# MachTestNguonSanXuat31072019.net
KiCad netlist of a schematic drawn in EAGLE
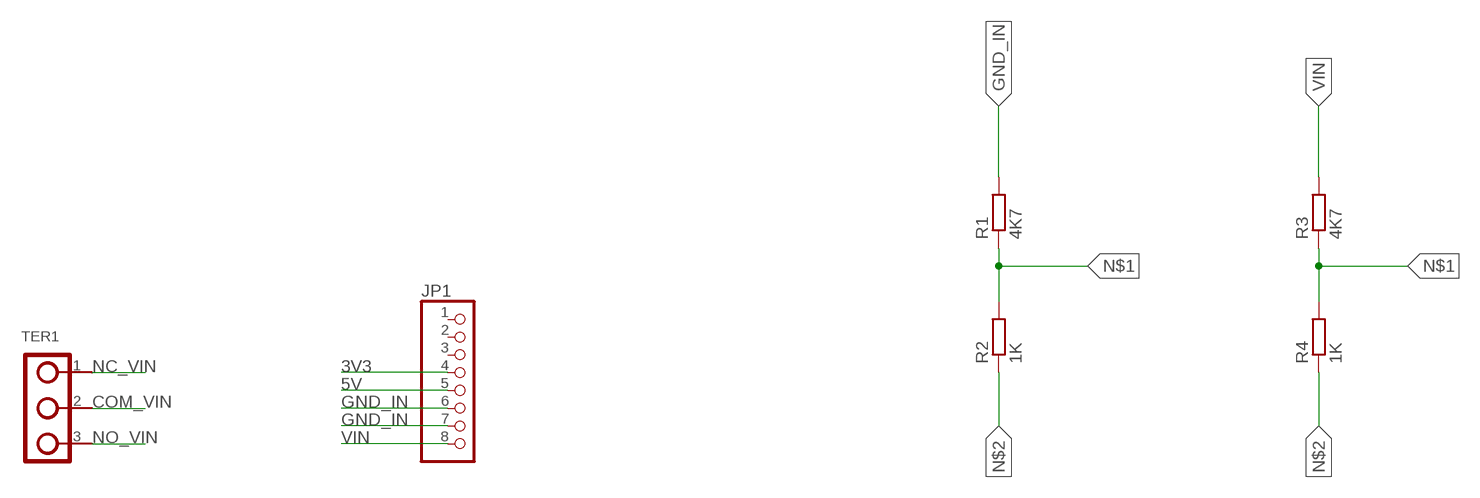
[diagram p0: schematic, sheet 1]

(export (version "E")
  (design (tool "Eeschema 10.0.6"))
  (components
    (comp (ref "JP1")
      (value "PINHD-1X8CLEANBIG")
      (footprint "eagle-import:1X08-CLEANBIG")
      (libsource (lib "eagle-import") (part "PINHD-1X8CLEANBIG"))
    )
    (comp (ref "R1")
      (value "4K7")
      (footprint "eagle-import:RCL_R0603")
      (libsource (lib "eagle-import") (part "RCL_R-EU_R0603"))
    )
    (comp (ref "R2")
      (value "1K")
      (footprint "eagle-import:RCL_R0603")
      (libsource (lib "eagle-import") (part "RCL_R-EU_R0603"))
    )
    (comp (ref "R3")
      (value "4K7")
      (footprint "eagle-import:RCL_R0603")
      (libsource (lib "eagle-import") (part "RCL_R-EU_R0603"))
    )
    (comp (ref "R4")
      (value "1K")
      (footprint "eagle-import:RCL_R0603")
      (libsource (lib "eagle-import") (part "RCL_R-EU_R0603"))
    )
    (comp (ref "TER1")
      (value "DOMINO-3")
      (footprint "eagle-import:DOMINO-3")
      (libsource (lib "eagle-import") (part "DOMINO-3"))
    )
  )
  (nets
    (net (code "1") (name "/3V3") (class "Default")
      (node (ref "JP1") (pin "4") (pinfunction "4_4") (pintype "passive"))
    )
    (net (code "2") (name "/5V") (class "Default")
      (node (ref "JP1") (pin "5") (pinfunction "5_5") (pintype "passive"))
    )
    (net (code "3") (name "/COM_VIN") (class "Default")
      (node (ref "TER1") (pin "2") (pinfunction "2_2") (pintype "bidirectional"))
    )
    (net (code "4") (name "/NC_VIN") (class "Default")
      (node (ref "TER1") (pin "1") (pinfunction "1_1") (pintype "bidirectional"))
    )
    (net (code "5") (name "/NO_VIN") (class "Default")
      (node (ref "TER1") (pin "3") (pinfunction "3_3") (pintype "bidirectional"))
    )
    (net (code "6") (name "GND_IN") (class "Default")
      (node (ref "JP1") (pin "6") (pinfunction "6_6") (pintype "passive"))
      (node (ref "JP1") (pin "7") (pinfunction "7_7") (pintype "passive"))
      (node (ref "R1") (pin "2") (pinfunction "2_2") (pintype "passive"))
    )
    (net (code "7") (name "N$1") (class "Default")
      (node (ref "R1") (pin "1") (pinfunction "1_1") (pintype "passive"))
      (node (ref "R2") (pin "2") (pinfunction "2_2") (pintype "passive"))
      (node (ref "R3") (pin "1") (pinfunction "1_1") (pintype "passive"))
      (node (ref "R4") (pin "2") (pinfunction "2_2") (pintype "passive"))
    )
    (net (code "8") (name "N$2") (class "Default")
      (node (ref "R2") (pin "1") (pinfunction "1_1") (pintype "passive"))
      (node (ref "R4") (pin "1") (pinfunction "1_1") (pintype "passive"))
    )
    (net (code "9") (name "VIN") (class "Default")
      (node (ref "JP1") (pin "8") (pinfunction "8_8") (pintype "passive"))
      (node (ref "R3") (pin "2") (pinfunction "2_2") (pintype "passive"))
    )
    (net (code "10") (name "unconnected-(JP1-Pad1)") (class "Default")
      (node (ref "JP1") (pin "1") (pinfunction "1_1") (pintype "passive"))
    )
    (net (code "11") (name "unconnected-(JP1-Pad2)") (class "Default")
      (node (ref "JP1") (pin "2") (pinfunction "2_2") (pintype "passive"))
    )
    (net (code "12") (name "unconnected-(JP1-Pad3)") (class "Default")
      (node (ref "JP1") (pin "3") (pinfunction "3_3") (pintype "passive"))
    )
  )
)
